# 6_-PEAKMETER_LEDS.net
KiCad netlist of a schematic drawn in Altium Designer
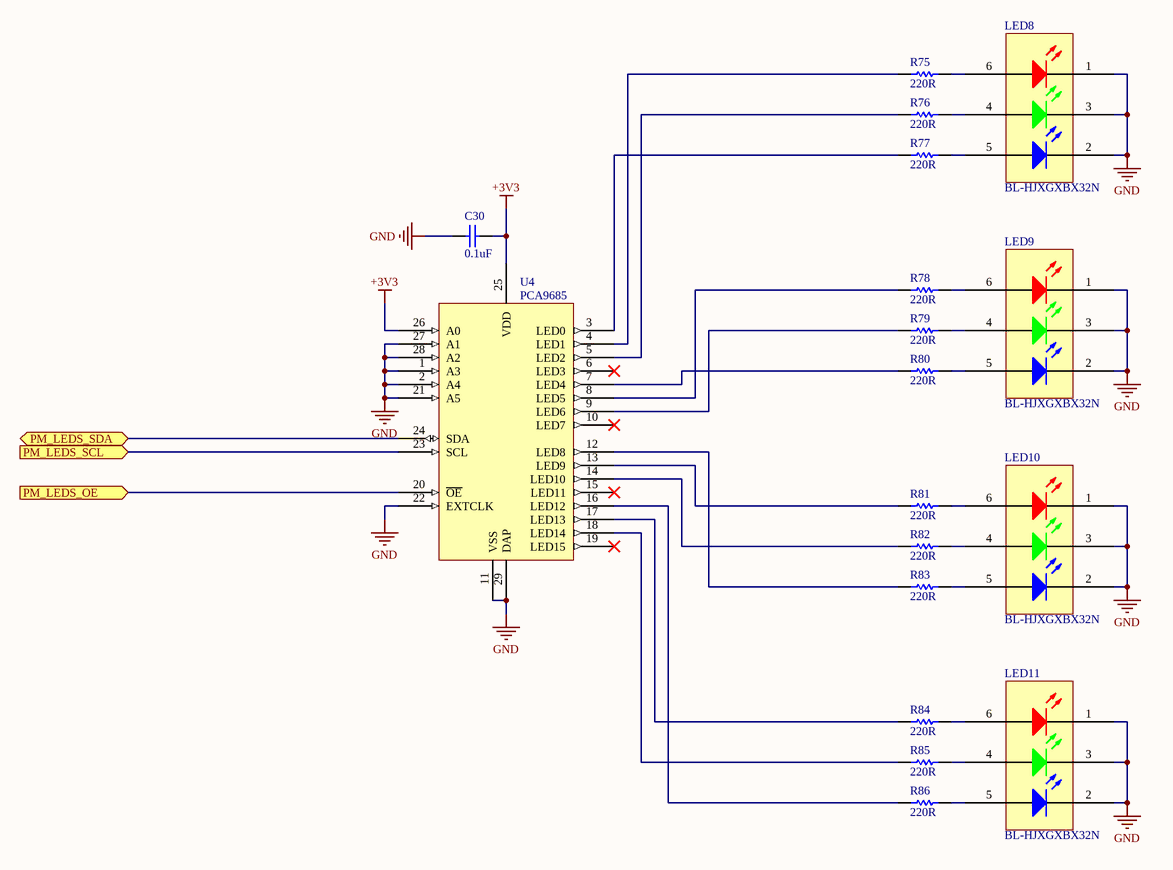
[diagram p0: [6]-PEAKMETER_LEDS.SchDoc]

(export (version "E")
  (design (tool "Eeschema 10.0.6"))
  (components
    (comp (ref "C30")
      (value "0.1uF")
      (footprint "CAPC1608N")
      (description "CAP CER 0.1UF 25V X7R 0603")
      (fields (field (name "TOLERANCE") "10%") (field (name "VOLTAGE") "25V"))
      (libsource (lib "bitsnio") (part "CC0603KRX7R8BB104"))
    )
    (comp (ref "LED8")
      (value "BL-HJXGXBX32N")
      (footprint "BL-HJXGXBX32N")
      (description "LED RGB 6PLCC SMD")
      (libsource (lib "bitsnio") (part "BL-HJXGXBX32N"))
    )
    (comp (ref "LED9")
      (value "BL-HJXGXBX32N")
      (footprint "BL-HJXGXBX32N")
      (description "LED RGB 6PLCC SMD")
      (libsource (lib "bitsnio") (part "BL-HJXGXBX32N"))
    )
    (comp (ref "LED10")
      (value "BL-HJXGXBX32N")
      (footprint "BL-HJXGXBX32N")
      (description "LED RGB 6PLCC SMD")
      (libsource (lib "bitsnio") (part "BL-HJXGXBX32N"))
    )
    (comp (ref "LED11")
      (value "BL-HJXGXBX32N")
      (footprint "BL-HJXGXBX32N")
      (description "LED RGB 6PLCC SMD")
      (libsource (lib "bitsnio") (part "BL-HJXGXBX32N"))
    )
    (comp (ref "R75")
      (value "220R")
      (footprint "RESC1608N")
      (description "RES SMD 220 OHM 5% 1/10W 0603")
      (fields (field (name "TOLERANCE") "5%"))
      (libsource (lib "bitsnio") (part "CRCW0603220RJNEA"))
    )
    (comp (ref "R76")
      (value "220R")
      (footprint "RESC1608N")
      (description "RES SMD 220 OHM 5% 1/10W 0603")
      (fields (field (name "TOLERANCE") "5%"))
      (libsource (lib "bitsnio") (part "CRCW0603220RJNEA"))
    )
    (comp (ref "R77")
      (value "220R")
      (footprint "RESC1608N")
      (description "RES SMD 220 OHM 5% 1/10W 0603")
      (fields (field (name "TOLERANCE") "5%"))
      (libsource (lib "bitsnio") (part "CRCW0603220RJNEA"))
    )
    (comp (ref "R78")
      (value "220R")
      (footprint "RESC1608N")
      (description "RES SMD 220 OHM 5% 1/10W 0603")
      (fields (field (name "TOLERANCE") "5%"))
      (libsource (lib "bitsnio") (part "CRCW0603220RJNEA"))
    )
    (comp (ref "R79")
      (value "220R")
      (footprint "RESC1608N")
      (description "RES SMD 220 OHM 5% 1/10W 0603")
      (fields (field (name "TOLERANCE") "5%"))
      (libsource (lib "bitsnio") (part "CRCW0603220RJNEA"))
    )
    (comp (ref "R80")
      (value "220R")
      (footprint "RESC1608N")
      (description "RES SMD 220 OHM 5% 1/10W 0603")
      (fields (field (name "TOLERANCE") "5%"))
      (libsource (lib "bitsnio") (part "CRCW0603220RJNEA"))
    )
    (comp (ref "R81")
      (value "220R")
      (footprint "RESC1608N")
      (description "RES SMD 220 OHM 5% 1/10W 0603")
      (fields (field (name "TOLERANCE") "5%"))
      (libsource (lib "bitsnio") (part "CRCW0603220RJNEA"))
    )
    (comp (ref "R82")
      (value "220R")
      (footprint "RESC1608N")
      (description "RES SMD 220 OHM 5% 1/10W 0603")
      (fields (field (name "TOLERANCE") "5%"))
      (libsource (lib "bitsnio") (part "CRCW0603220RJNEA"))
    )
    (comp (ref "R83")
      (value "220R")
      (footprint "RESC1608N")
      (description "RES SMD 220 OHM 5% 1/10W 0603")
      (fields (field (name "TOLERANCE") "5%"))
      (libsource (lib "bitsnio") (part "CRCW0603220RJNEA"))
    )
    (comp (ref "R84")
      (value "220R")
      (footprint "RESC1608N")
      (description "RES SMD 220 OHM 5% 1/10W 0603")
      (fields (field (name "TOLERANCE") "5%"))
      (libsource (lib "bitsnio") (part "CRCW0603220RJNEA"))
    )
    (comp (ref "R85")
      (value "220R")
      (footprint "RESC1608N")
      (description "RES SMD 220 OHM 5% 1/10W 0603")
      (fields (field (name "TOLERANCE") "5%"))
      (libsource (lib "bitsnio") (part "CRCW0603220RJNEA"))
    )
    (comp (ref "R86")
      (value "220R")
      (footprint "RESC1608N")
      (description "RES SMD 220 OHM 5% 1/10W 0603")
      (fields (field (name "TOLERANCE") "5%"))
      (libsource (lib "bitsnio") (part "CRCW0603220RJNEA"))
    )
    (comp (ref "U4")
      (value "PCA9685")
      (footprint "SOT788-1")
      (description "IC LED DRVR LIN DIM 25MA 28HVQFN")
      (libsource (lib "bitsnio") (part "IC_PCA9685BS,118"))
    )
  )
  (nets
    (net (code "1") (name "+3V3") (class "Default")
      (node (ref "C30") (pin "1") (pinfunction "1_1") (pintype "passive"))
      (node (ref "U4") (pin "25") (pinfunction "VDD_25") (pintype "passive"))
      (node (ref "U4") (pin "26") (pinfunction "A0_26") (pintype "input"))
    )
    (net (code "2") (name "/PM_LEDS_OE") (class "Default")
      (node (ref "U4") (pin "20") (pinfunction "~{OE}_20") (pintype "input"))
    )
    (net (code "3") (name "/PM_LEDS_SCL") (class "Default")
      (node (ref "U4") (pin "23") (pinfunction "SCL_23") (pintype "input"))
    )
    (net (code "4") (name "/PM_LEDS_SDA") (class "Default")
      (node (ref "U4") (pin "24") (pinfunction "SDA_24") (pintype "bidirectional"))
    )
    (net (code "5") (name "GND") (class "Default")
      (node (ref "C30") (pin "2") (pinfunction "2_2") (pintype "passive"))
      (node (ref "LED10") (pin "1") (pinfunction "1_1") (pintype "passive"))
      (node (ref "LED10") (pin "2") (pinfunction "2_2") (pintype "passive"))
      (node (ref "LED10") (pin "3") (pinfunction "3_3") (pintype "passive"))
      (node (ref "LED11") (pin "1") (pinfunction "1_1") (pintype "passive"))
      (node (ref "LED11") (pin "2") (pinfunction "2_2") (pintype "passive"))
      (node (ref "LED11") (pin "3") (pinfunction "3_3") (pintype "passive"))
      (node (ref "LED8") (pin "1") (pinfunction "1_1") (pintype "passive"))
      (node (ref "LED8") (pin "2") (pinfunction "2_2") (pintype "passive"))
      (node (ref "LED8") (pin "3") (pinfunction "3_3") (pintype "passive"))
      (node (ref "LED9") (pin "1") (pinfunction "1_1") (pintype "passive"))
      (node (ref "LED9") (pin "2") (pinfunction "2_2") (pintype "passive"))
      (node (ref "LED9") (pin "3") (pinfunction "3_3") (pintype "passive"))
      (node (ref "U4") (pin "1") (pinfunction "A3_1") (pintype "input"))
      (node (ref "U4") (pin "11") (pinfunction "VSS_11") (pintype "passive"))
      (node (ref "U4") (pin "2") (pinfunction "A4_2") (pintype "input"))
      (node (ref "U4") (pin "21") (pinfunction "A5_21") (pintype "input"))
      (node (ref "U4") (pin "22") (pinfunction "EXTCLK_22") (pintype "input"))
      (node (ref "U4") (pin "27") (pinfunction "A1_27") (pintype "input"))
      (node (ref "U4") (pin "28") (pinfunction "A2_28") (pintype "input"))
      (node (ref "U4") (pin "29") (pinfunction "DAP_29") (pintype "passive"))
    )
    (net (code "6") (name "Net-(LED8-Pad4)") (class "Default")
      (node (ref "LED8") (pin "4") (pinfunction "4_4") (pintype "passive"))
      (node (ref "R76") (pin "2") (pinfunction "2_2") (pintype "passive"))
    )
    (net (code "7") (name "Net-(LED8-Pad5)") (class "Default")
      (node (ref "LED8") (pin "5") (pinfunction "5_5") (pintype "passive"))
      (node (ref "R77") (pin "2") (pinfunction "2_2") (pintype "passive"))
    )
    (net (code "8") (name "Net-(LED8-Pad6)") (class "Default")
      (node (ref "LED8") (pin "6") (pinfunction "6_6") (pintype "passive"))
      (node (ref "R75") (pin "2") (pinfunction "2_2") (pintype "passive"))
    )
    (net (code "9") (name "Net-(LED9-Pad4)") (class "Default")
      (node (ref "LED9") (pin "4") (pinfunction "4_4") (pintype "passive"))
      (node (ref "R79") (pin "2") (pinfunction "2_2") (pintype "passive"))
    )
    (net (code "10") (name "Net-(LED9-Pad5)") (class "Default")
      (node (ref "LED9") (pin "5") (pinfunction "5_5") (pintype "passive"))
      (node (ref "R80") (pin "2") (pinfunction "2_2") (pintype "passive"))
    )
    (net (code "11") (name "Net-(LED9-Pad6)") (class "Default")
      (node (ref "LED9") (pin "6") (pinfunction "6_6") (pintype "passive"))
      (node (ref "R78") (pin "2") (pinfunction "2_2") (pintype "passive"))
    )
    (net (code "12") (name "Net-(LED10-Pad4)") (class "Default")
      (node (ref "LED10") (pin "4") (pinfunction "4_4") (pintype "passive"))
      (node (ref "R82") (pin "2") (pinfunction "2_2") (pintype "passive"))
    )
    (net (code "13") (name "Net-(LED10-Pad5)") (class "Default")
      (node (ref "LED10") (pin "5") (pinfunction "5_5") (pintype "passive"))
      (node (ref "R83") (pin "2") (pinfunction "2_2") (pintype "passive"))
    )
    (net (code "14") (name "Net-(LED10-Pad6)") (class "Default")
      (node (ref "LED10") (pin "6") (pinfunction "6_6") (pintype "passive"))
      (node (ref "R81") (pin "2") (pinfunction "2_2") (pintype "passive"))
    )
    (net (code "15") (name "Net-(LED11-Pad4)") (class "Default")
      (node (ref "LED11") (pin "4") (pinfunction "4_4") (pintype "passive"))
      (node (ref "R85") (pin "2") (pinfunction "2_2") (pintype "passive"))
    )
    (net (code "16") (name "Net-(LED11-Pad5)") (class "Default")
      (node (ref "LED11") (pin "5") (pinfunction "5_5") (pintype "passive"))
      (node (ref "R86") (pin "2") (pinfunction "2_2") (pintype "passive"))
    )
    (net (code "17") (name "Net-(LED11-Pad6)") (class "Default")
      (node (ref "LED11") (pin "6") (pinfunction "6_6") (pintype "passive"))
      (node (ref "R84") (pin "2") (pinfunction "2_2") (pintype "passive"))
    )
    (net (code "18") (name "Net-(U4-LED0)") (class "Default")
      (node (ref "R77") (pin "1") (pinfunction "1_1") (pintype "passive"))
      (node (ref "U4") (pin "3") (pinfunction "LED0_3") (pintype "output"))
    )
    (net (code "19") (name "Net-(U4-LED1)") (class "Default")
      (node (ref "R75") (pin "1") (pinfunction "1_1") (pintype "passive"))
      (node (ref "U4") (pin "4") (pinfunction "LED1_4") (pintype "output"))
    )
    (net (code "20") (name "Net-(U4-LED2)") (class "Default")
      (node (ref "R76") (pin "1") (pinfunction "1_1") (pintype "passive"))
      (node (ref "U4") (pin "5") (pinfunction "LED2_5") (pintype "output"))
    )
    (net (code "21") (name "Net-(U4-LED4)") (class "Default")
      (node (ref "R80") (pin "1") (pinfunction "1_1") (pintype "passive"))
      (node (ref "U4") (pin "7") (pinfunction "LED4_7") (pintype "output"))
    )
    (net (code "22") (name "Net-(U4-LED5)") (class "Default")
      (node (ref "R78") (pin "1") (pinfunction "1_1") (pintype "passive"))
      (node (ref "U4") (pin "8") (pinfunction "LED5_8") (pintype "output"))
    )
    (net (code "23") (name "Net-(U4-LED6)") (class "Default")
      (node (ref "R79") (pin "1") (pinfunction "1_1") (pintype "passive"))
      (node (ref "U4") (pin "9") (pinfunction "LED6_9") (pintype "output"))
    )
    (net (code "24") (name "Net-(U4-LED8)") (class "Default")
      (node (ref "R83") (pin "1") (pinfunction "1_1") (pintype "passive"))
      (node (ref "U4") (pin "12") (pinfunction "LED8_12") (pintype "output"))
    )
    (net (code "25") (name "Net-(U4-LED9)") (class "Default")
      (node (ref "R81") (pin "1") (pinfunction "1_1") (pintype "passive"))
      (node (ref "U4") (pin "13") (pinfunction "LED9_13") (pintype "output"))
    )
    (net (code "26") (name "Net-(U4-LED10)") (class "Default")
      (node (ref "R82") (pin "1") (pinfunction "1_1") (pintype "passive"))
      (node (ref "U4") (pin "14") (pinfunction "LED10_14") (pintype "output"))
    )
    (net (code "27") (name "Net-(U4-LED12)") (class "Default")
      (node (ref "R86") (pin "1") (pinfunction "1_1") (pintype "passive"))
      (node (ref "U4") (pin "16") (pinfunction "LED12_16") (pintype "output"))
    )
    (net (code "28") (name "Net-(U4-LED13)") (class "Default")
      (node (ref "R84") (pin "1") (pinfunction "1_1") (pintype "passive"))
      (node (ref "U4") (pin "17") (pinfunction "LED13_17") (pintype "output"))
    )
    (net (code "29") (name "Net-(U4-LED14)") (class "Default")
      (node (ref "R85") (pin "1") (pinfunction "1_1") (pintype "passive"))
      (node (ref "U4") (pin "18") (pinfunction "LED14_18") (pintype "output"))
    )
    (net (code "30") (name "unconnected-(U4-LED3-Pad6)") (class "Default")
      (node (ref "U4") (pin "6") (pinfunction "LED3_6") (pintype "output+no_connect"))
    )
    (net (code "31") (name "unconnected-(U4-LED7-Pad10)") (class "Default")
      (node (ref "U4") (pin "10") (pinfunction "LED7_10") (pintype "output+no_connect"))
    )
    (net (code "32") (name "unconnected-(U4-LED11-Pad15)") (class "Default")
      (node (ref "U4") (pin "15") (pinfunction "LED11_15") (pintype "output+no_connect"))
    )
    (net (code "33") (name "unconnected-(U4-LED15-Pad19)") (class "Default")
      (node (ref "U4") (pin "19") (pinfunction "LED15_19") (pintype "output+no_connect"))
    )
  )
)
